# BrauV2_Display.net
KiCad netlist of a schematic drawn in Altium Designer
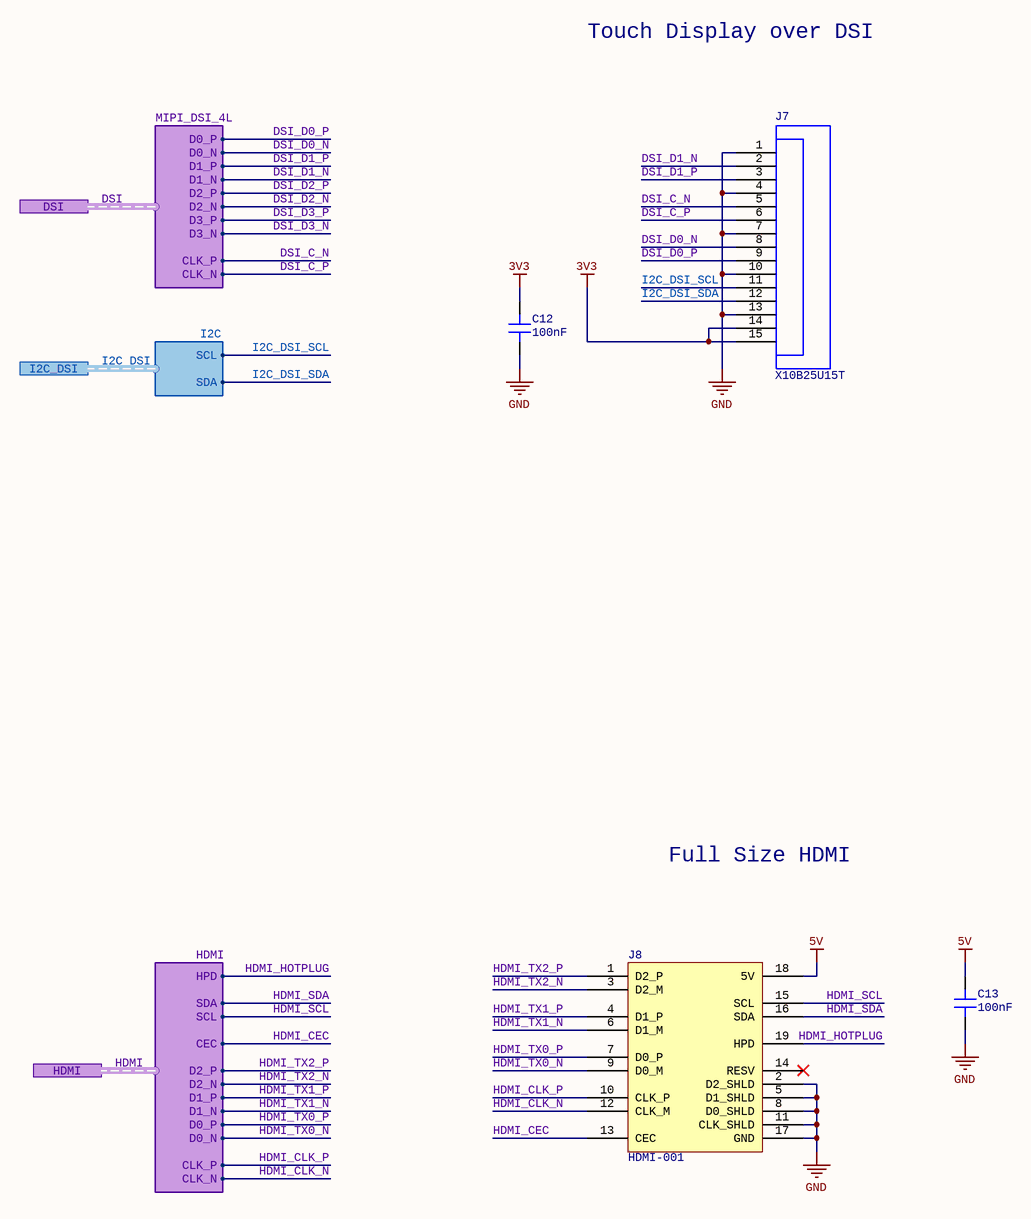
[diagram p0: BrauV2_Display.SchDoc]

(export (version "E")
  (design (tool "Eeschema 10.0.6"))
  (components
    (comp (ref "C12")
      (value "CC0402KRX5R6BB104")
      (footprint "SMD_CAP_0402(1005)_N")
      (description "100nF ±10% 10V X5R 0402 Multilayer Ceramic Capacitors MLCC - SMD/SMT RoHS")
      (fields (field (name "TOLERANCE") "10%") (field (name "CAPACITANCE") "100nF"))
      (libsource (lib "BrauV2_Capacitor") (part "100nF 0402 10V 10%"))
    )
    (comp (ref "C13")
      (value "CC0402KRX5R6BB104")
      (footprint "SMD_CAP_0402(1005)_N")
      (description "100nF ±10% 10V X5R 0402 Multilayer Ceramic Capacitors MLCC - SMD/SMT RoHS")
      (fields (field (name "TOLERANCE") "10%") (field (name "CAPACITANCE") "100nF"))
      (libsource (lib "BrauV2_Capacitor") (part "100nF 0402 10V 10%"))
    )
    (comp (ref "J7")
      (value "X10B25U15T")
      (footprint "X10B25U15T")
      (description "Contact,Top 15 0.039\"（1.00mm） 0.098\"（2.50mm） Slide Lock SMD FFC, FPC Connectors RoHS")
      (libsource (lib "BrauV2_Connector") (part "X10B25U15T"))
    )
    (comp (ref "J8")
      (value "HDMI-001")
      (footprint "HDMI-001")
      (description "BOOMELE(Boom Precision Elec) HDMIconnector 19 Female Horizontal SMD Audio & Video Connectors RoHS")
      (libsource (lib "BrauV2_Connector") (part "HDMI-001"))
    )
  )
  (nets
    (net (code "4") (name "/DSI_C_N") (class "Default")
      (node (ref "J7") (pin "5") (pinfunction "5_5") (pintype "passive"))
    )
    (net (code "5") (name "/DSI_C_P") (class "Default")
      (node (ref "J7") (pin "6") (pinfunction "6_6") (pintype "passive"))
    )
    (net (code "6") (name "/DSI_D0_N") (class "Default")
      (node (ref "J7") (pin "8") (pinfunction "8_8") (pintype "passive"))
    )
    (net (code "7") (name "/DSI_D0_P") (class "Default")
      (node (ref "J7") (pin "9") (pinfunction "9_9") (pintype "passive"))
    )
    (net (code "8") (name "/DSI_D1_N") (class "Default")
      (node (ref "J7") (pin "2") (pinfunction "2_2") (pintype "passive"))
    )
    (net (code "9") (name "/DSI_D1_P") (class "Default")
      (node (ref "J7") (pin "3") (pinfunction "3_3") (pintype "passive"))
    )
    (net (code "15") (name "/HDMI_CEC") (class "Default")
      (node (ref "J8") (pin "13") (pinfunction "CEC_13") (pintype "passive"))
    )
    (net (code "16") (name "/HDMI_CLK_N") (class "Default")
      (node (ref "J8") (pin "12") (pinfunction "CLK_M_12") (pintype "passive"))
    )
    (net (code "17") (name "/HDMI_CLK_P") (class "Default")
      (node (ref "J8") (pin "10") (pinfunction "CLK_P_10") (pintype "passive"))
    )
    (net (code "18") (name "/HDMI_HOTPLUG") (class "Default")
      (node (ref "J8") (pin "19") (pinfunction "HPD_19") (pintype "passive"))
    )
    (net (code "19") (name "/HDMI_SCL") (class "Default")
      (node (ref "J8") (pin "15") (pinfunction "SCL_15") (pintype "passive"))
    )
    (net (code "20") (name "/HDMI_SDA") (class "Default")
      (node (ref "J8") (pin "16") (pinfunction "SDA_16") (pintype "passive"))
    )
    (net (code "21") (name "/HDMI_TX0_N") (class "Default")
      (node (ref "J8") (pin "9") (pinfunction "D0_M_9") (pintype "passive"))
    )
    (net (code "22") (name "/HDMI_TX0_P") (class "Default")
      (node (ref "J8") (pin "7") (pinfunction "D0_P_7") (pintype "passive"))
    )
    (net (code "23") (name "/HDMI_TX1_N") (class "Default")
      (node (ref "J8") (pin "6") (pinfunction "D1_M_6") (pintype "passive"))
    )
    (net (code "24") (name "/HDMI_TX1_P") (class "Default")
      (node (ref "J8") (pin "4") (pinfunction "D1_P_4") (pintype "passive"))
    )
    (net (code "25") (name "/HDMI_TX2_N") (class "Default")
      (node (ref "J8") (pin "3") (pinfunction "D2_M_3") (pintype "passive"))
    )
    (net (code "26") (name "/HDMI_TX2_P") (class "Default")
      (node (ref "J8") (pin "1") (pinfunction "D2_P_1") (pintype "passive"))
    )
    (net (code "28") (name "/I2C_DSI_SCL") (class "Default")
      (node (ref "J7") (pin "11") (pinfunction "11_11") (pintype "passive"))
    )
    (net (code "29") (name "/I2C_DSI_SDA") (class "Default")
      (node (ref "J7") (pin "12") (pinfunction "12_12") (pintype "passive"))
    )
    (net (code "31") (name "3V3") (class "Default")
      (node (ref "C12") (pin "2") (pinfunction "2_2") (pintype "passive"))
      (node (ref "J7") (pin "14") (pinfunction "14_14") (pintype "passive"))
      (node (ref "J7") (pin "15") (pinfunction "15_15") (pintype "passive"))
    )
    (net (code "32") (name "5V") (class "Default")
      (node (ref "C13") (pin "2") (pinfunction "2_2") (pintype "passive"))
      (node (ref "J8") (pin "18") (pinfunction "5V_18") (pintype "passive"))
    )
    (net (code "33") (name "GND") (class "Default")
      (node (ref "C12") (pin "1") (pinfunction "1_1") (pintype "passive"))
      (node (ref "C13") (pin "1") (pinfunction "1_1") (pintype "passive"))
      (node (ref "J7") (pin "1") (pinfunction "1_1") (pintype "passive"))
      (node (ref "J7") (pin "10") (pinfunction "10_10") (pintype "passive"))
      (node (ref "J7") (pin "13") (pinfunction "13_13") (pintype "passive"))
      (node (ref "J7") (pin "4") (pinfunction "4_4") (pintype "passive"))
      (node (ref "J7") (pin "7") (pinfunction "7_7") (pintype "passive"))
      (node (ref "J8") (pin "11") (pinfunction "CLK_SHLD_11") (pintype "passive"))
      (node (ref "J8") (pin "17") (pinfunction "GND_17") (pintype "passive"))
      (node (ref "J8") (pin "2") (pinfunction "D2_SHLD_2") (pintype "passive"))
      (node (ref "J8") (pin "5") (pinfunction "D1_SHLD_5") (pintype "passive"))
      (node (ref "J8") (pin "8") (pinfunction "D0_SHLD_8") (pintype "passive"))
    )
    (net (code "34") (name "unconnected-(J8-RESV-Pad14)") (class "Default")
      (node (ref "J8") (pin "14") (pinfunction "RESV_14") (pintype "passive+no_connect"))
    )
  )
)
